# mini_exp_v1-1-0c.net
KiCad netlist of a schematic drawn in EAGLE
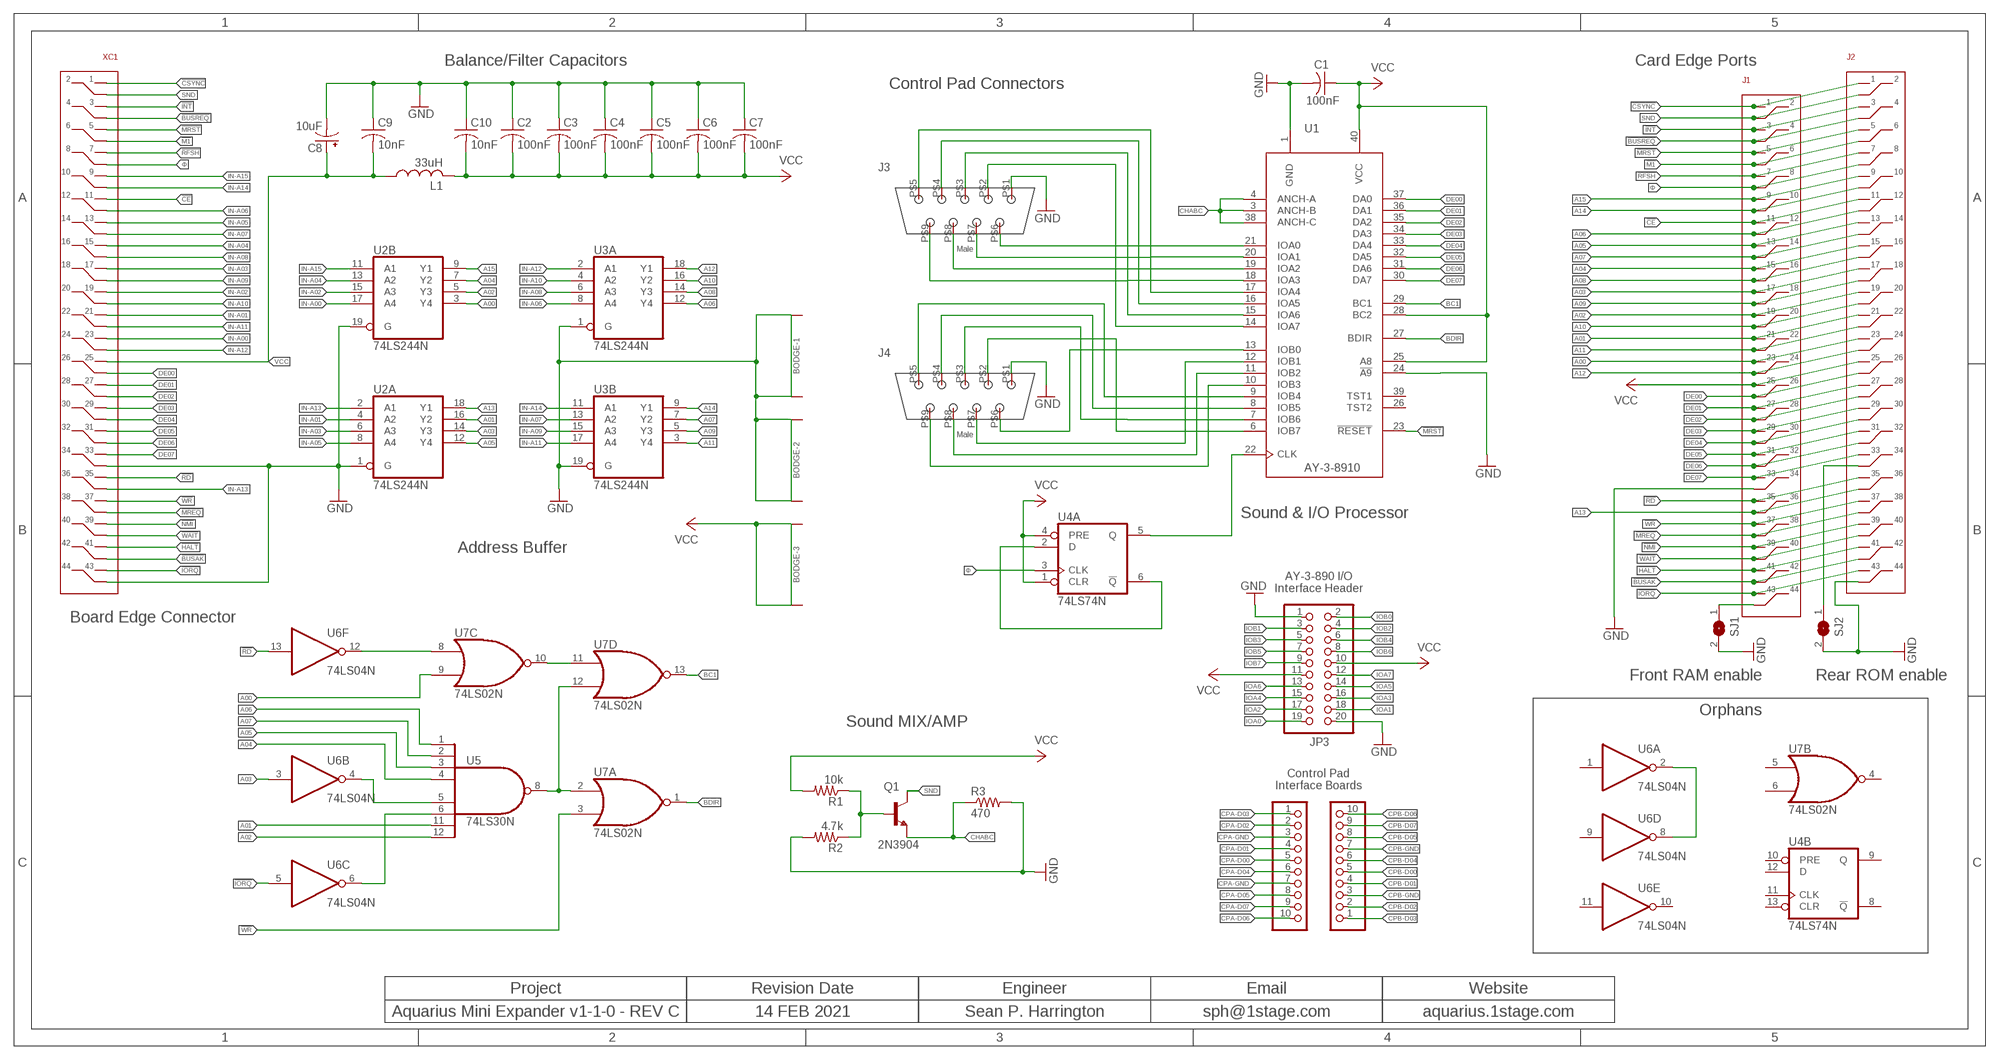
[diagram p0: schematic, sheet 1]

(export (version "E")
  (design (tool "Eeschema 10.0.6"))
  (components
    (comp (ref "C1")
      (value "100nF")
      (footprint "eagle-import:C050-025X095")
      (libsource (lib "eagle-import") (part "C-US050-025X095"))
    )
    (comp (ref "C2")
      (value "100nF")
      (footprint "eagle-import:C050-025X095")
      (libsource (lib "eagle-import") (part "C-US050-025X095"))
    )
    (comp (ref "C3")
      (value "100nF")
      (footprint "eagle-import:C050-025X095")
      (libsource (lib "eagle-import") (part "C-US050-025X095"))
    )
    (comp (ref "C4")
      (value "100nF")
      (footprint "eagle-import:C050-025X095")
      (libsource (lib "eagle-import") (part "C-US050-025X095"))
    )
    (comp (ref "C5")
      (value "100nF")
      (footprint "eagle-import:C050-025X095")
      (libsource (lib "eagle-import") (part "C-US050-025X095"))
    )
    (comp (ref "C6")
      (value "100nF")
      (footprint "eagle-import:C050-025X095")
      (libsource (lib "eagle-import") (part "C-US050-025X095"))
    )
    (comp (ref "C7")
      (value "100nF")
      (footprint "eagle-import:C050-025X095")
      (libsource (lib "eagle-import") (part "C-US050-025X095"))
    )
    (comp (ref "C8")
      (value "10uF")
      (footprint "eagle-import:E22-6")
      (libsource (lib "eagle-import") (part "CPOL-USE22-6AXIAL"))
    )
    (comp (ref "C9")
      (value "10nF")
      (footprint "eagle-import:C075-032X103")
      (libsource (lib "eagle-import") (part "C-US075-032X103"))
    )
    (comp (ref "C10")
      (value "10nF")
      (footprint "eagle-import:C075-032X103")
      (libsource (lib "eagle-import") (part "C-US075-032X103"))
    )
    (comp (ref "J1")
      (value "CR22A-44D-2.54DS(70)STRAIGHT")
      (footprint "eagle-import:CR22A-44D-2.54DS(70)")
      (libsource (lib "eagle-import") (part "CR22A-44D-2.54DS(70)STRAIGHT"))
    )
    (comp (ref "J2")
      (value "CR22A-44D-2.54DS(70)STRAIGHT")
      (footprint "eagle-import:CR22A-44D-2.54DS(70)")
      (libsource (lib "eagle-import") (part "CR22A-44D-2.54DS(70)STRAIGHT"))
    )
    (comp (ref "J3")
      (value "DB9-MALE-RA")
      (footprint "eagle-import:DB9-MALE-RA")
      (libsource (lib "eagle-import") (part "DB9-MALE-RA"))
    )
    (comp (ref "J4")
      (value "DB9-MALE-RA")
      (footprint "eagle-import:DB9-MALE-RA")
      (libsource (lib "eagle-import") (part "DB9-MALE-RA"))
    )
    (comp (ref "JP1")
      (value "PINHD-1X10")
      (footprint "eagle-import:1X10")
      (libsource (lib "eagle-import") (part "PINHD-1X10"))
    )
    (comp (ref "JP2")
      (value "PINHD-1X10")
      (footprint "eagle-import:1X10")
      (libsource (lib "eagle-import") (part "PINHD-1X10"))
    )
    (comp (ref "JP3")
      (value "PINHD-2X10")
      (footprint "eagle-import:2X10")
      (libsource (lib "eagle-import") (part "PINHD-2X10"))
    )
    (comp (ref "L1")
      (value "33uH")
      (footprint "eagle-import:0204_5")
      (libsource (lib "eagle-import") (part "L-US0204/5"))
    )
    (comp (ref "Q1")
      (value "2N3904")
      (footprint "eagle-import:TO92")
      (libsource (lib "eagle-import") (part "2N3904"))
    )
    (comp (ref "R1")
      (value "10k")
      (footprint "eagle-import:0207_7")
      (libsource (lib "eagle-import") (part "R-US_0207/7"))
    )
    (comp (ref "R2")
      (value "4.7k")
      (footprint "eagle-import:0207_7")
      (libsource (lib "eagle-import") (part "R-US_0207/7"))
    )
    (comp (ref "R3")
      (value "470")
      (footprint "eagle-import:0207_7")
      (libsource (lib "eagle-import") (part "R-US_0207/7"))
    )
    (comp (ref "SJ1") (value "SJ") (footprint "eagle-import:SJ") (libsource (lib "eagle-import") (part "SJ")))
    (comp (ref "SJ2") (value "SJ") (footprint "eagle-import:SJ") (libsource (lib "eagle-import") (part "SJ")))
    (comp (ref "U1")
      (value "AY-3-8910")
      (footprint "eagle-import:RAD38910-DIL40-6")
      (libsource (lib "eagle-import") (part "RAD38910DIL40-6"))
    )
    (comp (ref "U2")
      (value "74LS244N")
      (footprint "eagle-import:DIL20")
      (libsource (lib "eagle-import") (part "74244NLS"))
    )
    (comp (ref "U3")
      (value "74LS244N")
      (footprint "eagle-import:DIL20")
      (libsource (lib "eagle-import") (part "74244NLS"))
    )
    (comp (ref "U4")
      (value "74LS74N")
      (footprint "eagle-import:DIL14")
      (libsource (lib "eagle-import") (part "7474NLS"))
    )
    (comp (ref "U5")
      (value "74LS30N")
      (footprint "eagle-import:DIL14")
      (libsource (lib "eagle-import") (part "7430NLS"))
    )
    (comp (ref "U6")
      (value "74LS04N")
      (footprint "eagle-import:DIL14")
      (libsource (lib "eagle-import") (part "7404NLS"))
    )
    (comp (ref "U7")
      (value "74LS02N")
      (footprint "eagle-import:DIL14")
      (libsource (lib "eagle-import") (part "7402NLS"))
    )
    (comp (ref "XC1")
      (value "AQ-CART-EDGE")
      (footprint "eagle-import:AQ-CART-EDGE")
      (libsource (lib "eagle-import") (part "AQ-CART-EDGE"))
    )
    (comp (ref "XX01")
      (value "AQ-MX-BODGE-1")
      (footprint "eagle-import:AQ-MX-BODGE-1")
      (libsource (lib "eagle-import") (part "AQ-MX-BODGE-1"))
    )
    (comp (ref "XX02")
      (value "AQ-MX-BODGE-2")
      (footprint "eagle-import:AQ-MX-BODGE-2")
      (libsource (lib "eagle-import") (part "AQ-MX-BODGE-2"))
    )
    (comp (ref "XX03")
      (value "AQ-MX-BODGE-3")
      (footprint "eagle-import:AQ-MX-BODGE-3")
      (libsource (lib "eagle-import") (part "AQ-MX-BODGE-3"))
    )
  )
  (nets
    (net (code "1") (name "/~{BUSAK}") (class "Default")
      (node (ref "J1") (pin "P$42") (pinfunction "X42_P$42") (pintype "bidirectional"))
      (node (ref "J2") (pin "P$42") (pinfunction "X42_P$42") (pintype "bidirectional"))
      (node (ref "XC1") (pin "P$42") (pinfunction "X42_P$42") (pintype "bidirectional"))
    )
    (net (code "2") (name "/~{BUSREQ}") (class "Default")
      (node (ref "J1") (pin "P$4") (pinfunction "X4_P$4") (pintype "bidirectional"))
      (node (ref "J2") (pin "P$4") (pinfunction "X4_P$4") (pintype "bidirectional"))
      (node (ref "XC1") (pin "P$4") (pinfunction "X4_P$4") (pintype "bidirectional"))
    )
    (net (code "3") (name "/~{CE}") (class "Default")
      (node (ref "J1") (pin "P$11") (pinfunction "X11_P$11") (pintype "bidirectional"))
      (node (ref "J2") (pin "P$11") (pinfunction "X11_P$11") (pintype "bidirectional"))
      (node (ref "XC1") (pin "P$11") (pinfunction "X11_P$11") (pintype "bidirectional"))
    )
    (net (code "4") (name "/~{CSYNC}") (class "Default")
      (node (ref "J1") (pin "P$1") (pinfunction "X1_P$1") (pintype "bidirectional"))
      (node (ref "J2") (pin "P$1") (pinfunction "X1_P$1") (pintype "bidirectional"))
      (node (ref "XC1") (pin "P$1") (pinfunction "X1_P$1") (pintype "bidirectional"))
    )
    (net (code "5") (name "/~{HALT}") (class "Default")
      (node (ref "J1") (pin "P$41") (pinfunction "X41_P$41") (pintype "bidirectional"))
      (node (ref "J2") (pin "P$41") (pinfunction "X41_P$41") (pintype "bidirectional"))
      (node (ref "XC1") (pin "P$41") (pinfunction "X41_P$41") (pintype "bidirectional"))
    )
    (net (code "6") (name "/~{INT}") (class "Default")
      (node (ref "J1") (pin "P$3") (pinfunction "X3_P$3") (pintype "bidirectional"))
      (node (ref "J2") (pin "P$3") (pinfunction "X3_P$3") (pintype "bidirectional"))
      (node (ref "XC1") (pin "P$3") (pinfunction "X3_P$3") (pintype "bidirectional"))
    )
    (net (code "7") (name "/~{IORQ}") (class "Default")
      (node (ref "J1") (pin "P$43") (pinfunction "X43_P$43") (pintype "bidirectional"))
      (node (ref "J2") (pin "P$43") (pinfunction "X43_P$43") (pintype "bidirectional"))
      (node (ref "U6") (pin "5") (pinfunction "I_5") (pintype "input"))
      (node (ref "XC1") (pin "P$43") (pinfunction "X43_P$43") (pintype "bidirectional"))
    )
    (net (code "8") (name "/~{M1}") (class "Default")
      (node (ref "J1") (pin "P$6") (pinfunction "X6_P$6") (pintype "bidirectional"))
      (node (ref "J2") (pin "P$6") (pinfunction "X6_P$6") (pintype "bidirectional"))
      (node (ref "XC1") (pin "P$6") (pinfunction "X6_P$6") (pintype "bidirectional"))
    )
    (net (code "9") (name "/~{MREQ}") (class "Default")
      (node (ref "J1") (pin "P$38") (pinfunction "X38_P$38") (pintype "bidirectional"))
      (node (ref "J2") (pin "P$38") (pinfunction "X38_P$38") (pintype "bidirectional"))
      (node (ref "XC1") (pin "P$38") (pinfunction "X38_P$38") (pintype "bidirectional"))
    )
    (net (code "10") (name "/~{MRST}") (class "Default")
      (node (ref "J1") (pin "P$5") (pinfunction "X5_P$5") (pintype "bidirectional"))
      (node (ref "J2") (pin "P$5") (pinfunction "X5_P$5") (pintype "bidirectional"))
      (node (ref "U1") (pin "23") (pinfunction "~{RESET}_23") (pintype "bidirectional"))
      (node (ref "XC1") (pin "P$5") (pinfunction "X5_P$5") (pintype "bidirectional"))
    )
    (net (code "11") (name "/~{NMI}") (class "Default")
      (node (ref "J1") (pin "P$39") (pinfunction "X39_P$39") (pintype "bidirectional"))
      (node (ref "J2") (pin "P$39") (pinfunction "X39_P$39") (pintype "bidirectional"))
      (node (ref "XC1") (pin "P$39") (pinfunction "X39_P$39") (pintype "bidirectional"))
    )
    (net (code "12") (name "/~{RD}") (class "Default")
      (node (ref "J1") (pin "P$35") (pinfunction "X35_P$35") (pintype "bidirectional"))
      (node (ref "J2") (pin "P$35") (pinfunction "X35_P$35") (pintype "bidirectional"))
      (node (ref "U6") (pin "13") (pinfunction "I_13") (pintype "input"))
      (node (ref "XC1") (pin "P$35") (pinfunction "X35_P$35") (pintype "bidirectional"))
    )
    (net (code "13") (name "/~{RFSH}") (class "Default")
      (node (ref "J1") (pin "P$7") (pinfunction "X7_P$7") (pintype "bidirectional"))
      (node (ref "J2") (pin "P$7") (pinfunction "X7_P$7") (pintype "bidirectional"))
      (node (ref "XC1") (pin "P$7") (pinfunction "X7_P$7") (pintype "bidirectional"))
    )
    (net (code "14") (name "/~{WAIT}") (class "Default")
      (node (ref "J1") (pin "P$40") (pinfunction "X40_P$40") (pintype "bidirectional"))
      (node (ref "J2") (pin "P$40") (pinfunction "X40_P$40") (pintype "bidirectional"))
      (node (ref "XC1") (pin "P$40") (pinfunction "X40_P$40") (pintype "bidirectional"))
    )
    (net (code "15") (name "/~{WR}") (class "Default")
      (node (ref "J1") (pin "P$37") (pinfunction "X37_P$37") (pintype "bidirectional"))
      (node (ref "J2") (pin "P$37") (pinfunction "X37_P$37") (pintype "bidirectional"))
      (node (ref "U7") (pin "3") (pinfunction "I1_3") (pintype "input"))
      (node (ref "XC1") (pin "P$37") (pinfunction "X37_P$37") (pintype "bidirectional"))
    )
    (net (code "16") (name "A00") (class "Default")
      (node (ref "J1") (pin "P$23") (pinfunction "X23_P$23") (pintype "bidirectional"))
      (node (ref "J2") (pin "P$23") (pinfunction "X23_P$23") (pintype "bidirectional"))
      (node (ref "U2") (pin "3") (pinfunction "Y4_3") (pintype "tri_state"))
      (node (ref "U7") (pin "9") (pinfunction "I1_9") (pintype "input"))
    )
    (net (code "17") (name "A01") (class "Default")
      (node (ref "J1") (pin "P$21") (pinfunction "X21_P$21") (pintype "bidirectional"))
      (node (ref "J2") (pin "P$21") (pinfunction "X21_P$21") (pintype "bidirectional"))
      (node (ref "U2") (pin "16") (pinfunction "Y2_16") (pintype "tri_state"))
      (node (ref "U5") (pin "11") (pinfunction "I6_11") (pintype "input"))
    )
    (net (code "18") (name "A02") (class "Default")
      (node (ref "J1") (pin "P$19") (pinfunction "X19_P$19") (pintype "bidirectional"))
      (node (ref "J2") (pin "P$19") (pinfunction "X19_P$19") (pintype "bidirectional"))
      (node (ref "U2") (pin "5") (pinfunction "Y3_5") (pintype "tri_state"))
      (node (ref "U5") (pin "12") (pinfunction "I7_12") (pintype "input"))
    )
    (net (code "19") (name "A03") (class "Default")
      (node (ref "J1") (pin "P$17") (pinfunction "X17_P$17") (pintype "bidirectional"))
      (node (ref "J2") (pin "P$17") (pinfunction "X17_P$17") (pintype "bidirectional"))
      (node (ref "U2") (pin "14") (pinfunction "Y3_14") (pintype "tri_state"))
      (node (ref "U6") (pin "3") (pinfunction "I_3") (pintype "input"))
    )
    (net (code "20") (name "A04") (class "Default")
      (node (ref "J1") (pin "P$15") (pinfunction "X15_P$15") (pintype "bidirectional"))
      (node (ref "J2") (pin "P$15") (pinfunction "X15_P$15") (pintype "bidirectional"))
      (node (ref "U2") (pin "7") (pinfunction "Y2_7") (pintype "tri_state"))
      (node (ref "U5") (pin "4") (pinfunction "I3_4") (pintype "input"))
    )
    (net (code "21") (name "A05") (class "Default")
      (node (ref "J1") (pin "P$13") (pinfunction "X13_P$13") (pintype "bidirectional"))
      (node (ref "J2") (pin "P$13") (pinfunction "X13_P$13") (pintype "bidirectional"))
      (node (ref "U2") (pin "12") (pinfunction "Y4_12") (pintype "tri_state"))
      (node (ref "U5") (pin "3") (pinfunction "I2_3") (pintype "input"))
    )
    (net (code "22") (name "A06") (class "Default")
      (node (ref "J1") (pin "P$12") (pinfunction "X12_P$12") (pintype "bidirectional"))
      (node (ref "J2") (pin "P$12") (pinfunction "X12_P$12") (pintype "bidirectional"))
      (node (ref "U3") (pin "12") (pinfunction "Y4_12") (pintype "tri_state"))
      (node (ref "U5") (pin "1") (pinfunction "I0_1") (pintype "input"))
    )
    (net (code "23") (name "A07") (class "Default")
      (node (ref "J1") (pin "P$14") (pinfunction "X14_P$14") (pintype "bidirectional"))
      (node (ref "J2") (pin "P$14") (pinfunction "X14_P$14") (pintype "bidirectional"))
      (node (ref "U3") (pin "7") (pinfunction "Y2_7") (pintype "tri_state"))
      (node (ref "U5") (pin "2") (pinfunction "I1_2") (pintype "input"))
    )
    (net (code "24") (name "A08") (class "Default")
      (node (ref "J1") (pin "P$16") (pinfunction "X16_P$16") (pintype "bidirectional"))
      (node (ref "J2") (pin "P$16") (pinfunction "X16_P$16") (pintype "bidirectional"))
      (node (ref "U3") (pin "14") (pinfunction "Y3_14") (pintype "tri_state"))
    )
    (net (code "25") (name "A09") (class "Default")
      (node (ref "J1") (pin "P$18") (pinfunction "X18_P$18") (pintype "bidirectional"))
      (node (ref "J2") (pin "P$18") (pinfunction "X18_P$18") (pintype "bidirectional"))
      (node (ref "U3") (pin "5") (pinfunction "Y3_5") (pintype "tri_state"))
    )
    (net (code "26") (name "A10") (class "Default")
      (node (ref "J1") (pin "P$20") (pinfunction "X20_P$20") (pintype "bidirectional"))
      (node (ref "J2") (pin "P$20") (pinfunction "X20_P$20") (pintype "bidirectional"))
      (node (ref "U3") (pin "16") (pinfunction "Y2_16") (pintype "tri_state"))
    )
    (net (code "27") (name "A11") (class "Default")
      (node (ref "J1") (pin "P$22") (pinfunction "X22_P$22") (pintype "bidirectional"))
      (node (ref "J2") (pin "P$22") (pinfunction "X22_P$22") (pintype "bidirectional"))
      (node (ref "U3") (pin "3") (pinfunction "Y4_3") (pintype "tri_state"))
    )
    (net (code "28") (name "A12") (class "Default")
      (node (ref "J1") (pin "P$24") (pinfunction "X24_P$24") (pintype "bidirectional"))
      (node (ref "J2") (pin "P$24") (pinfunction "X24_P$24") (pintype "bidirectional"))
      (node (ref "U3") (pin "18") (pinfunction "Y1_18") (pintype "tri_state"))
    )
    (net (code "29") (name "A13") (class "Default")
      (node (ref "J1") (pin "P$36") (pinfunction "X36_P$36") (pintype "bidirectional"))
      (node (ref "J2") (pin "P$36") (pinfunction "X36_P$36") (pintype "bidirectional"))
      (node (ref "U2") (pin "18") (pinfunction "Y1_18") (pintype "tri_state"))
    )
    (net (code "30") (name "A14") (class "Default")
      (node (ref "J1") (pin "P$10") (pinfunction "X10_P$10") (pintype "bidirectional"))
      (node (ref "J2") (pin "P$10") (pinfunction "X10_P$10") (pintype "bidirectional"))
      (node (ref "U3") (pin "9") (pinfunction "Y1_9") (pintype "tri_state"))
    )
    (net (code "31") (name "A15") (class "Default")
      (node (ref "J1") (pin "P$9") (pinfunction "X9_P$9") (pintype "bidirectional"))
      (node (ref "J2") (pin "P$9") (pinfunction "X9_P$9") (pintype "bidirectional"))
      (node (ref "U2") (pin "9") (pinfunction "Y1_9") (pintype "tri_state"))
    )
    (net (code "32") (name "BC1") (class "Default")
      (node (ref "U1") (pin "29") (pinfunction "BC1_29") (pintype "bidirectional"))
      (node (ref "U7") (pin "13") (pinfunction "O_13") (pintype "output"))
    )
    (net (code "33") (name "BDIR") (class "Default")
      (node (ref "U1") (pin "27") (pinfunction "BDIR_27") (pintype "bidirectional"))
      (node (ref "U7") (pin "1") (pinfunction "O_1") (pintype "output"))
    )
    (net (code "34") (name "CHABC") (class "Default")
      (node (ref "Q1") (pin "3") (pinfunction "E_3") (pintype "passive"))
      (node (ref "R3") (pin "1") (pinfunction "1_1") (pintype "passive"))
      (node (ref "U1") (pin "3") (pinfunction "ANCH-B_3") (pintype "bidirectional"))
      (node (ref "U1") (pin "38") (pinfunction "ANCH-C_38") (pintype "bidirectional"))
      (node (ref "U1") (pin "4") (pinfunction "ANCH-A_4") (pintype "bidirectional"))
    )
    (net (code "35") (name "CPA-D00") (class "Default")
      (node (ref "JP1") (pin "5") (pinfunction "5_5") (pintype "passive"))
    )
    (net (code "36") (name "CPA-D01") (class "Default")
      (node (ref "JP1") (pin "4") (pinfunction "4_4") (pintype "passive"))
    )
    (net (code "37") (name "CPA-D02") (class "Default")
      (node (ref "JP1") (pin "2") (pinfunction "2_2") (pintype "passive"))
    )
    (net (code "38") (name "CPA-D03") (class "Default")
      (node (ref "JP1") (pin "1") (pinfunction "1_1") (pintype "passive"))
    )
    (net (code "39") (name "CPA-D04") (class "Default")
      (node (ref "JP1") (pin "6") (pinfunction "6_6") (pintype "passive"))
    )
    (net (code "40") (name "CPA-D05") (class "Default")
      (node (ref "JP1") (pin "8") (pinfunction "8_8") (pintype "passive"))
    )
    (net (code "41") (name "CPA-D06") (class "Default")
      (node (ref "JP1") (pin "10") (pinfunction "10_10") (pintype "passive"))
    )
    (net (code "42") (name "CPA-D07") (class "Default")
      (node (ref "JP1") (pin "9") (pinfunction "9_9") (pintype "passive"))
    )
    (net (code "43") (name "CPA-GND") (class "Default")
      (node (ref "JP1") (pin "3") (pinfunction "3_3") (pintype "passive"))
      (node (ref "JP1") (pin "7") (pinfunction "7_7") (pintype "passive"))
    )
    (net (code "44") (name "CPB-D00") (class "Default")
      (node (ref "JP2") (pin "5") (pinfunction "5_5") (pintype "passive"))
    )
    (net (code "45") (name "CPB-D01") (class "Default")
      (node (ref "JP2") (pin "4") (pinfunction "4_4") (pintype "passive"))
    )
    (net (code "46") (name "CPB-D02") (class "Default")
      (node (ref "JP2") (pin "2") (pinfunction "2_2") (pintype "passive"))
    )
    (net (code "47") (name "CPB-D03") (class "Default")
      (node (ref "JP2") (pin "1") (pinfunction "1_1") (pintype "passive"))
    )
    (net (code "48") (name "CPB-D04") (class "Default")
      (node (ref "JP2") (pin "6") (pinfunction "6_6") (pintype "passive"))
    )
    (net (code "49") (name "CPB-D05") (class "Default")
      (node (ref "JP2") (pin "8") (pinfunction "8_8") (pintype "passive"))
    )
    (net (code "50") (name "CPB-D06") (class "Default")
      (node (ref "JP2") (pin "10") (pinfunction "10_10") (pintype "passive"))
    )
    (net (code "51") (name "CPB-D07") (class "Default")
      (node (ref "JP2") (pin "9") (pinfunction "9_9") (pintype "passive"))
    )
    (net (code "52") (name "CPB-GND") (class "Default")
      (node (ref "JP2") (pin "3") (pinfunction "3_3") (pintype "passive"))
      (node (ref "JP2") (pin "7") (pinfunction "7_7") (pintype "passive"))
    )
    (net (code "53") (name "DE00") (class "Default")
      (node (ref "J1") (pin "P$26") (pinfunction "X26_P$26") (pintype "bidirectional"))
      (node (ref "J2") (pin "P$26") (pinfunction "X26_P$26") (pintype "bidirectional"))
      (node (ref "U1") (pin "37") (pinfunction "DA0_37") (pintype "bidirectional"))
      (node (ref "XC1") (pin "P$26") (pinfunction "X26_P$26") (pintype "bidirectional"))
    )
    (net (code "54") (name "DE01") (class "Default")
      (node (ref "J1") (pin "P$27") (pinfunction "X27_P$27") (pintype "bidirectional"))
      (node (ref "J2") (pin "P$27") (pinfunction "X27_P$27") (pintype "bidirectional"))
      (node (ref "U1") (pin "36") (pinfunction "DA1_36") (pintype "bidirectional"))
      (node (ref "XC1") (pin "P$27") (pinfunction "X27_P$27") (pintype "bidirectional"))
    )
    (net (code "55") (name "DE02") (class "Default")
      (node (ref "J1") (pin "P$28") (pinfunction "X28_P$28") (pintype "bidirectional"))
      (node (ref "J2") (pin "P$28") (pinfunction "X28_P$28") (pintype "bidirectional"))
      (node (ref "U1") (pin "35") (pinfunction "DA2_35") (pintype "bidirectional"))
      (node (ref "XC1") (pin "P$28") (pinfunction "X28_P$28") (pintype "bidirectional"))
    )
    (net (code "56") (name "DE03") (class "Default")
      (node (ref "J1") (pin "P$29") (pinfunction "X29_P$29") (pintype "bidirectional"))
      (node (ref "J2") (pin "P$29") (pinfunction "X29_P$29") (pintype "bidirectional"))
      (node (ref "U1") (pin "34") (pinfunction "DA3_34") (pintype "bidirectional"))
      (node (ref "XC1") (pin "P$29") (pinfunction "X29_P$29") (pintype "bidirectional"))
    )
    (net (code "57") (name "DE04") (class "Default")
      (node (ref "J1") (pin "P$30") (pinfunction "X30_P$30") (pintype "bidirectional"))
      (node (ref "J2") (pin "P$30") (pinfunction "X30_P$30") (pintype "bidirectional"))
      (node (ref "U1") (pin "33") (pinfunction "DA4_33") (pintype "bidirectional"))
      (node (ref "XC1") (pin "P$30") (pinfunction "X30_P$30") (pintype "bidirectional"))
    )
    (net (code "58") (name "DE05") (class "Default")
      (node (ref "J1") (pin "P$31") (pinfunction "X31_P$31") (pintype "bidirectional"))
      (node (ref "J2") (pin "P$31") (pinfunction "X31_P$31") (pintype "bidirectional"))
      (node (ref "U1") (pin "32") (pinfunction "DA5_32") (pintype "bidirectional"))
      (node (ref "XC1") (pin "P$31") (pinfunction "X31_P$31") (pintype "bidirectional"))
    )
    (net (code "59") (name "DE06") (class "Default")
      (node (ref "J1") (pin "P$32") (pinfunction "X32_P$32") (pintype "bidirectional"))
      (node (ref "J2") (pin "P$32") (pinfunction "X32_P$32") (pintype "bidirectional"))
      (node (ref "U1") (pin "31") (pinfunction "DA6_31") (pintype "bidirectional"))
      (node (ref "XC1") (pin "P$32") (pinfunction "X32_P$32") (pintype "bidirectional"))
    )
    (net (code "60") (name "DE07") (class "Default")
      (node (ref "J1") (pin "P$33") (pinfunction "X33_P$33") (pintype "bidirectional"))
      (node (ref "J2") (pin "P$33") (pinfunction "X33_P$33") (pintype "bidirectional"))
      (node (ref "U1") (pin "30") (pinfunction "DA7_30") (pintype "bidirectional"))
      (node (ref "XC1") (pin "P$33") (pinfunction "X33_P$33") (pintype "bidirectional"))
    )
    (net (code "61") (name "GND") (class "Default")
      (node (ref "C1") (pin "2") (pinfunction "2_2") (pintype "passive"))
      (node (ref "C10") (pin "1") (pinfunction "1_1") (pintype "passive"))
      (node (ref "C2") (pin "1") (pinfunction "1_1") (pintype "passive"))
      (node (ref "C3") (pin "1") (pinfunction "1_1") (pintype "passive"))
      (node (ref "C4") (pin "1") (pinfunction "1_1") (pintype "passive"))
      (node (ref "C5") (pin "1") (pinfunction "1_1") (pintype "passive"))
      (node (ref "C6") (pin "1") (pinfunction "1_1") (pintype "passive"))
      (node (ref "C7") (pin "1") (pinfunction "1_1") (pintype "passive"))
      (node (ref "C8") (pin "-") (pinfunction "-_-") (pintype "passive"))
      (node (ref "C9") (pin "1") (pinfunction "1_1") (pintype "passive"))
      (node (ref "J1") (pin "P$34") (pinfunction "X34_P$34") (pintype "bidirectional"))
      (node (ref "J2") (pin "P$44") (pinfunction "X44_P$44") (pintype "bidirectional"))
      (node (ref "J3") (pin "P$1") (pinfunction "P$1_P$1") (pintype "bidirectional"))
      (node (ref "J4") (pin "P$1") (pinfunction "P$1_P$1") (pintype "bidirectional"))
      (node (ref "JP3") (pin "1") (pinfunction "1_1") (pintype "passive"))
      (node (ref "JP3") (pin "20") (pinfunction "20_20") (pintype "passive"))
      (node (ref "R2") (pin "2") (pinfunction "2_2") (pintype "passive"))
      (node (ref "R3") (pin "2") (pinfunction "2_2") (pintype "passive"))
      (node (ref "SJ1") (pin "2") (pinfunction "2_2") (pintype "passive"))
      (node (ref "SJ2") (pin "2") (pinfunction "2_2") (pintype "passive"))
      (node (ref "U1") (pin "1") (pinfunction "GND_1") (pintype "power_in"))
      (node (ref "U1") (pin "24") (pinfunction "~{A9}_24") (pintype "bidirectional"))
      (node (ref "U2") (pin "1") (pinfunction "G_1") (pintype "input"))
      (node (ref "U2") (pin "19") (pinfunction "G_19") (pintype "input"))
      (node (ref "U3") (pin "1") (pinfunction "G_1") (pintype "input"))
      (node (ref "U3") (pin "19") (pinfunction "G_19") (pintype "input"))
      (node (ref "XC1") (pin "P$34") (pinfunction "X34_P$34") (pintype "bidirectional"))
      (node (ref "XC1") (pin "P$44") (pinfunction "X44_P$44") (pintype "bidirectional"))
      (node (ref "XX01") (pin "P$1") (pinfunction "P$1_P$1") (pintype "bidirectional"))
      (node (ref "XX01") (pin "P$2") (pinfunction "P$2_P$2") (pintype "bidirectional"))
      (node (ref "XX02") (pin "P$1") (pinfunction "P$1_P$1") (pintype "bidirectional"))
      (node (ref "XX02") (pin "P$2") (pinfunction "P$2_P$2") (pintype "bidirectional"))
    )
    (net (code "62") (name "IN-A00") (class "Default")
      (node (ref "U2") (pin "17") (pinfunction "A4_17") (pintype "input"))
      (node (ref "XC1") (pin "P$23") (pinfunction "X23_P$23") (pintype "bidirectional"))
    )
    (net (code "63") (name "IN-A01") (class "Default")
      (node (ref "U2") (pin "4") (pinfunction "A2_4") (pintype "input"))
      (node (ref "XC1") (pin "P$21") (pinfunction "X21_P$21") (pintype "bidirectional"))
    )
    (net (code "64") (name "IN-A02") (class "Default")
      (node (ref "U2") (pin "15") (pinfunction "A3_15") (pintype "input"))
      (node (ref "XC1") (pin "P$19") (pinfunction "X19_P$19") (pintype "bidirectional"))
    )
    (net (code "65") (name "IN-A03") (class "Default")
      (node (ref "U2") (pin "6") (pinfunction "A3_6") (pintype "input"))
      (node (ref "XC1") (pin "P$17") (pinfunction "X17_P$17") (pintype "bidirectional"))
    )
    (net (code "66") (name "IN-A04") (class "Default")
      (node (ref "U2") (pin "13") (pinfunction "A2_13") (pintype "input"))
      (node (ref "XC1") (pin "P$15") (pinfunction "X15_P$15") (pintype "bidirectional"))
    )
    (net (code "67") (name "IN-A05") (class "Default")
      (node (ref "U2") (pin "8") (pinfunction "A4_8") (pintype "input"))
      (node (ref "XC1") (pin "P$13") (pinfunction "X13_P$13") (pintype "bidirectional"))
    )
    (net (code "68") (name "IN-A06") (class "Default")
      (node (ref "U3") (pin "8") (pinfunction "A4_8") (pintype "input"))
      (node (ref "XC1") (pin "P$12") (pinfunction "X12_P$12") (pintype "bidirectional"))
    )
    (net (code "69") (name "IN-A07") (class "Default")
      (node (ref "U3") (pin "13") (pinfunction "A2_13") (pintype "input"))
      (node (ref "XC1") (pin "P$14") (pinfunction "X14_P$14") (pintype "bidirectional"))
    )
    (net (code "70") (name "IN-A08") (class "Default")
      (node (ref "U3") (pin "6") (pinfunction "A3_6") (pintype "input"))
      (node (ref "XC1") (pin "P$16") (pinfunction "X16_P$16") (pintype "bidirectional"))
    )
    (net (code "71") (name "IN-A09") (class "Default")
      (node (ref "U3") (pin "15") (pinfunction "A3_15") (pintype "input"))
      (node (ref "XC1") (pin "P$18") (pinfunction "X18_P$18") (pintype "bidirectional"))
    )
    (net (code "72") (name "IN-A10") (class "Default")
      (node (ref "U3") (pin "4") (pinfunction "A2_4") (pintype "input"))
      (node (ref "XC1") (pin "P$20") (pinfunction "X20_P$20") (pintype "bidirectional"))
    )
    (net (code "73") (name "IN-A11") (class "Default")
      (node (ref "U3") (pin "17") (pinfunction "A4_17") (pintype "input"))
      (node (ref "XC1") (pin "P$22") (pinfunction "X22_P$22") (pintype "bidirectional"))
    )
    (net (code "74") (name "IN-A12") (class "Default")
      (node (ref "U3") (pin "2") (pinfunction "A1_2") (pintype "input"))
      (node (ref "XC1") (pin "P$24") (pinfunction "X24_P$24") (pintype "bidirectional"))
    )
    (net (code "75") (name "IN-A13") (class "Default")
      (node (ref "U2") (pin "2") (pinfunction "A1_2") (pintype "input"))
      (node (ref "XC1") (pin "P$36") (pinfunction "X36_P$36") (pintype "bidirectional"))
    )
    (net (code "76") (name "IN-A14") (class "Default")
      (node (ref "U3") (pin "11") (pinfunction "A1_11") (pintype "input"))
      (node (ref "XC1") (pin "P$10") (pinfunction "X10_P$10") (pintype "bidirectional"))
    )
    (net (code "77") (name "IN-A15") (class "Default")
      (node (ref "U2") (pin "11") (pinfunction "A1_11") (pintype "input"))
      (node (ref "XC1") (pin "P$9") (pinfunction "X9_P$9") (pintype "bidirectional"))
    )
    (net (code "78") (name "IOA0") (class "Default")
      (node (ref "J3") (pin "P$6") (pinfunction "P$6_P$6") (pintype "bidirectional"))
      (node (ref "JP3") (pin "19") (pinfunction "19_19") (pintype "passive"))
      (node (ref "U1") (pin "21") (pinfunction "IOA0_21") (pintype "bidirectional"))
    )
    (net (code "79") (name "IOA1") (class "Default")
      (node (ref "J3") (pin "P$7") (pinfunction "P$7_P$7") (pintype "bidirectional"))
      (node (ref "JP3") (pin "18") (pinfunction "18_18") (pintype "passive"))
      (node (ref "U1") (pin "20") (pinfunction "IOA1_20") (pintype "bidirectional"))
    )
    (net (code "80") (name "IOA2") (class "Default")
      (node (ref "J3") (pin "P$8") (pinfunction "P$8_P$8") (pintype "bidirectional"))
      (node (ref "JP3") (pin "17") (pinfunction "17_17") (pintype "passive"))
      (node (ref "U1") (pin "19") (pinfunction "IOA2_19") (pintype "bidirectional"))
    )
    (net (code "81") (name "IOA3") (class "Default")
      (node (ref "J3") (pin "P$9") (pinfunction "P$9_P$9") (pintype "bidirectional"))
      (node (ref "JP3") (pin "16") (pinfunction "16_16") (pintype "passive"))
      (node (ref "U1") (pin "18") (pinfunction "IOA3_18") (pintype "bidirectional"))
    )
    (net (code "82") (name "IOA4") (class "Default")
      (node (ref "J3") (pin "P$5") (pinfunction "P$5_P$5") (pintype "bidirectional"))
      (node (ref "JP3") (pin "15") (pinfunction "15_15") (pintype "passive"))
      (node (ref "U1") (pin "17") (pinfunction "IOA4_17") (pintype "bidirectional"))
    )
    (net (code "83") (name "IOA5") (class "Default")
      (node (ref "J3") (pin "P$4") (pinfunction "P$4_P$4") (pintype "bidirectional"))
      (node (ref "JP3") (pin "14") (pinfunction "14_14") (pintype "passive"))
      (node (ref "U1") (pin "16") (pinfunction "IOA5_16") (pintype "bidirectional"))
    )
    (net (code "84") (name "IOA6") (class "Default")
      (node (ref "J3") (pin "P$3") (pinfunction "P$3_P$3") (pintype "bidirectional"))
      (node (ref "JP3") (pin "13") (pinfunction "13_13") (pintype "passive"))
      (node (ref "U1") (pin "15") (pinfunction "IOA6_15") (pintype "bidirectional"))
    )
    (net (code "85") (name "IOA7") (class "Default")
      (node (ref "J3") (pin "P$2") (pinfunction "P$2_P$2") (pintype "bidirectional"))
      (node (ref "JP3") (pin "12") (pinfunction "12_12") (pintype "passive"))
      (node (ref "U1") (pin "14") (pinfunction "IOA7_14") (pintype "bidirectional"))
    )
    (net (code "86") (name "IOB0") (class "Default")
      (node (ref "J4") (pin "P$6") (pinfunction "P$6_P$6") (pintype "bidirectional"))
      (node (ref "JP3") (pin "2") (pinfunction "2_2") (pintype "passive"))
      (node (ref "U1") (pin "13") (pinfunction "IOB0_13") (pintype "bidirectional"))
    )
    (net (code "87") (name "IOB1") (class "Default")
      (node (ref "J4") (pin "P$7") (pinfunction "P$7_P$7") (pintype "bidirectional"))
      (node (ref "JP3") (pin "3") (pinfunction "3_3") (pintype "passive"))
      (node (ref "U1") (pin "12") (pinfunction "IOB1_12") (pintype "bidirectional"))
    )
    (net (code "88") (name "IOB2") (class "Default")
      (node (ref "J4") (pin "P$8") (pinfunction "P$8_P$8") (pintype "bidirectional"))
      (node (ref "JP3") (pin "4") (pinfunction "4_4") (pintype "passive"))
      (node (ref "U1") (pin "11") (pinfunction "IOB2_11") (pintype "bidirectional"))
    )
    (net (code "89") (name "IOB3") (class "Default")
      (node (ref "J4") (pin "P$9") (pinfunction "P$9_P$9") (pintype "bidirectional"))
      (node (ref "JP3") (pin "5") (pinfunction "5_5") (pintype "passive"))
      (node (ref "U1") (pin "10") (pinfunction "IOB3_10") (pintype "bidirectional"))
    )
    (net (code "90") (name "IOB4") (class "Default")
      (node (ref "J4") (pin "P$5") (pinfunction "P$5_P$5") (pintype "bidirectional"))
      (node (ref "JP3") (pin "6") (pinfunction "6_6") (pintype "passive"))
      (node (ref "U1") (pin "9") (pinfunction "IOB4_9") (pintype "bidirectional"))
    )
    (net (code "91") (name "IOB5") (class "Default")
      (node (ref "J4") (pin "P$4") (pinfunction "P$4_P$4") (pintype "bidirectional"))
      (node (ref "JP3") (pin "7") (pinfunction "7_7") (pintype "passive"))
      (node (ref "U1") (pin "8") (pinfunction "IOB5_8") (pintype "bidirectional"))
    )
    (net (code "92") (name "IOB6") (class "Default")
      (node (ref "J4") (pin "P$3") (pinfunction "P$3_P$3") (pintype "bidirectional"))
      (node (ref "JP3") (pin "8") (pinfunction "8_8") (pintype "passive"))
      (node (ref "U1") (pin "7") (pinfunction "IOB6_7") (pintype "bidirectional"))
    )
    (net (code "93") (name "IOB7") (class "Default")
      (node (ref "J4") (pin "P$2") (pinfunction "P$2_P$2") (pintype "bidirectional"))
      (node (ref "JP3") (pin "9") (pinfunction "9_9") (pintype "passive"))
      (node (ref "U1") (pin "6") (pinfunction "IOB7_6") (pintype "bidirectional"))
    )
    (net (code "94") (name "Net-(J1-X44)") (class "Default")
      (node (ref "J1") (pin "P$44") (pinfunction "X44_P$44") (pintype "bidirectional"))
      (node (ref "SJ1") (pin "1") (pinfunction "1_1") (pintype "passive"))
    )
    (net (code "95") (name "Net-(J2-X34)") (class "Default")
      (node (ref "J2") (pin "P$34") (pinfunction "X34_P$34") (pintype "bidirectional"))
      (node (ref "SJ2") (pin "1") (pinfunction "1_1") (pintype "passive"))
    )
    (net (code "96") (name "Net-(Q1-B)") (class "Default")
      (node (ref "Q1") (pin "2") (pinfunction "B_2") (pintype "passive"))
      (node (ref "R1") (pin "1") (pinfunction "1_1") (pintype "passive"))
      (node (ref "R2") (pin "1") (pinfunction "1_1") (pintype "passive"))
    )
    (net (code "97") (name "Net-(U1-CLK)") (class "Default")
      (node (ref "U1") (pin "22") (pinfunction "CLK_22") (pintype "input"))
      (node (ref "U4") (pin "5") (pinfunction "Q_5") (pintype "output"))
    )
    (net (code "98") (name "Net-(U4A-D)") (class "Default")
      (node (ref "U4") (pin "2") (pinfunction "D_2") (pintype "input"))
      (node (ref "U4") (pin "6") (pinfunction "~{Q}_6") (pintype "output"))
    )
    (net (code "99") (name "Net-(U5A-I4)") (class "Default")
      (node (ref "U5") (pin "5") (pinfunction "I4_5") (pintype "input"))
      (node (ref "U6") (pin "4") (pinfunction "O_4") (pintype "output"))
    )
    (net (code "100") (name "Net-(U5A-I5)") (class "Default")
      (node (ref "U5") (pin "6") (pinfunction "I5_6") (pintype "input"))
      (node (ref "U6") (pin "6") (pinfunction "O_6") (pintype "output"))
    )
    (net (code "101") (name "Net-(U5A-O)") (class "Default")
      (node (ref "U5") (pin "8") (pinfunction "O_8") (pintype "output"))
      (node (ref "U7") (pin "12") (pinfunction "I1_12") (pintype "input"))
      (node (ref "U7") (pin "2") (pinfunction "I0_2") (pintype "input"))
    )
    (net (code "102") (name "Net-(U6A-O)") (class "Default")
      (node (ref "U6") (pin "2") (pinfunction "O_2") (pintype "output"))
      (node (ref "U6") (pin "8") (pinfunction "O_8") (pintype "output"))
    )
    (net (code "103") (name "Net-(U6F-O)") (class "Default")
      (node (ref "U6") (pin "12") (pinfunction "O_12") (pintype "output"))
      (node (ref "U7") (pin "8") (pinfunction "I0_8") (pintype "input"))
    )
    (net (code "104") (name "Net-(U7C-O)") (class "Default")
      (node (ref "U7") (pin "10") (pinfunction "O_10") (pintype "output"))
      (node (ref "U7") (pin "11") (pinfunction "I0_11") (pintype "input"))
    )
    (net (code "105") (name "SND") (class "Default")
      (node (ref "J1") (pin "P$2") (pinfunction "X2_P$2") (pintype "bidirectional"))
      (node (ref "J2") (pin "P$2") (pinfunction "X2_P$2") (pintype "bidirectional"))
      (node (ref "Q1") (pin "1") (pinfunction "C_1") (pintype "passive"))
      (node (ref "XC1") (pin "P$2") (pinfunction "X2_P$2") (pintype "bidirectional"))
    )
    (net (code "106") (name "VCC") (class "Default")
      (node (ref "C1") (pin "1") (pinfunction "1_1") (pintype "passive"))
      (node (ref "C10") (pin "2") (pinfunction "2_2") (pintype "passive"))
      (node (ref "C2") (pin "2") (pinfunction "2_2") (pintype "passive"))
      (node (ref "C3") (pin "2") (pinfunction "2_2") (pintype "passive"))
      (node (ref "C4") (pin "2") (pinfunction "2_2") (pintype "passive"))
      (node (ref "C5") (pin "2") (pinfunction "2_2") (pintype "passive"))
      (node (ref "C6") (pin "2") (pinfunction "2_2") (pintype "passive"))
      (node (ref "C7") (pin "2") (pinfunction "2_2") (pintype "passive"))
      (node (ref "C8") (pin "+") (pinfunction "+_+") (pintype "passive"))
      (node (ref "C9") (pin "2") (pinfunction "2_2") (pintype "passive"))
      (node (ref "J1") (pin "P$25") (pinfunction "X25_P$25") (pintype "bidirectional"))
      (node (ref "J2") (pin "P$25") (pinfunction "X25_P$25") (pintype "bidirectional"))
      (node (ref "JP3") (pin "10") (pinfunction "10_10") (pintype "passive"))
      (node (ref "JP3") (pin "11") (pinfunction "11_11") (pintype "passive"))
      (node (ref "L1") (pin "1") (pinfunction "1_1") (pintype "passive"))
      (node (ref "L1") (pin "2") (pinfunction "2_2") (pintype "passive"))
      (node (ref "R1") (pin "2") (pinfunction "2_2") (pintype "passive"))
      (node (ref "U1") (pin "25") (pinfunction "A8_25") (pintype "bidirectional"))
      (node (ref "U1") (pin "28") (pinfunction "BC2_28") (pintype "bidirectional"))
      (node (ref "U1") (pin "40") (pinfunction "VCC_40") (pintype "power_in"))
      (node (ref "U4") (pin "1") (pinfunction "CLR_1") (pintype "input"))
      (node (ref "U4") (pin "4") (pinfunction "PRE_4") (pintype "input"))
      (node (ref "XC1") (pin "P$25") (pinfunction "X25_P$25") (pintype "bidirectional"))
      (node (ref "XX03") (pin "P$1") (pinfunction "P$1_P$1") (pintype "bidirectional"))
      (node (ref "XX03") (pin "P$2") (pinfunction "P$2_P$2") (pintype "bidirectional"))
    )
    (net (code "107") (name "unconnected-(U1-TST1-Pad39)") (class "Default")
      (node (ref "U1") (pin "39") (pinfunction "TST1_39") (pintype "bidirectional"))
    )
    (net (code "108") (name "unconnected-(U1-TST2-Pad26)") (class "Default")
      (node (ref "U1") (pin "26") (pinfunction "TST2_26") (pintype "bidirectional"))
    )
    (net (code "109") (name "unconnected-(U4B-CLK-Pad11)") (class "Default")
      (node (ref "U4") (pin "11") (pinfunction "CLK_11") (pintype "input"))
    )
    (net (code "110") (name "unconnected-(U4B-CLR-Pad13)") (class "Default")
      (node (ref "U4") (pin "13") (pinfunction "CLR_13") (pintype "input"))
    )
    (net (code "111") (name "unconnected-(U4B-D-Pad12)") (class "Default")
      (node (ref "U4") (pin "12") (pinfunction "D_12") (pintype "input"))
    )
    (net (code "112") (name "unconnected-(U4B-PRE-Pad10)") (class "Default")
      (node (ref "U4") (pin "10") (pinfunction "PRE_10") (pintype "input"))
    )
    (net (code "113") (name "unconnected-(U4B-Q-Pad9)") (class "Default")
      (node (ref "U4") (pin "9") (pinfunction "Q_9") (pintype "output"))
    )
    (net (code "114") (name "unconnected-(U4B-~{Q}-Pad8)") (class "Default")
      (node (ref "U4") (pin "8") (pinfunction "~{Q}_8") (pintype "output"))
    )
    (net (code "115") (name "unconnected-(U6A-I-Pad1)") (class "Default")
      (node (ref "U6") (pin "1") (pinfunction "I_1") (pintype "input"))
    )
    (net (code "116") (name "unconnected-(U6D-I-Pad9)") (class "Default")
      (node (ref "U6") (pin "9") (pinfunction "I_9") (pintype "input"))
    )
    (net (code "117") (name "unconnected-(U6E-I-Pad11)") (class "Default")
      (node (ref "U6") (pin "11") (pinfunction "I_11") (pintype "input"))
    )
    (net (code "118") (name "unconnected-(U6E-O-Pad10)") (class "Default")
      (node (ref "U6") (pin "10") (pinfunction "O_10") (pintype "output"))
    )
    (net (code "119") (name "unconnected-(U7B-I0-Pad5)") (class "Default")
      (node (ref "U7") (pin "5") (pinfunction "I0_5") (pintype "input"))
    )
    (net (code "120") (name "unconnected-(U7B-I1-Pad6)") (class "Default")
      (node (ref "U7") (pin "6") (pinfunction "I1_6") (pintype "input"))
    )
    (net (code "121") (name "unconnected-(U7B-O-Pad4)") (class "Default")
      (node (ref "U7") (pin "4") (pinfunction "O_4") (pintype "output"))
    )
    (net (code "122") (name "Φ") (class "Default")
      (node (ref "J1") (pin "P$8") (pinfunction "X8_P$8") (pintype "bidirectional"))
      (node (ref "J2") (pin "P$8") (pinfunction "X8_P$8") (pintype "bidirectional"))
      (node (ref "U4") (pin "3") (pinfunction "CLK_3") (pintype "input"))
      (node (ref "XC1") (pin "P$8") (pinfunction "X8_P$8") (pintype "bidirectional"))
    )
  )
)
